# dc-dc_24V_5A_0_2.net
KiCad netlist of a schematic drawn in EAGLE
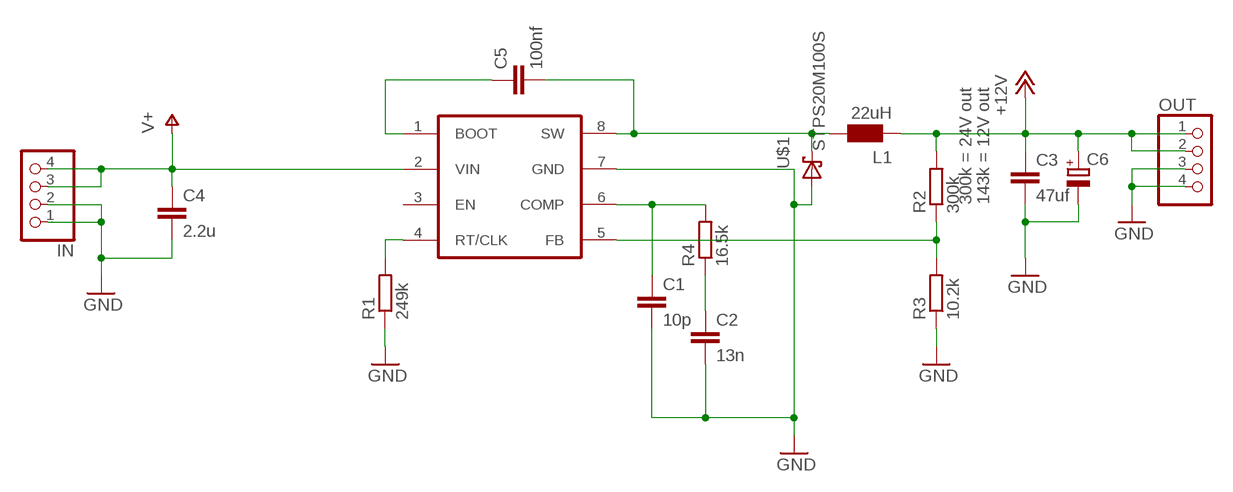
[diagram p0: schematic, sheet 1]

(export (version "E")
  (design (tool "Eeschema 10.0.6"))
  (components
    (comp (ref "C1")
      (value "10p")
      (footprint "eagle-import:C0805")
      (libsource (lib "eagle-import") (part "C-EUC0805"))
    )
    (comp (ref "C2")
      (value "13n")
      (footprint "eagle-import:C1206")
      (libsource (lib "eagle-import") (part "C-EUC1206"))
    )
    (comp (ref "C3")
      (value "47uf")
      (footprint "eagle-import:C1210")
      (libsource (lib "eagle-import") (part "C-EUC1210"))
    )
    (comp (ref "C4")
      (value "2.2u")
      (footprint "eagle-import:C1210")
      (libsource (lib "eagle-import") (part "C-EUC1210"))
    )
    (comp (ref "C5")
      (value "100nf")
      (footprint "eagle-import:C0805")
      (libsource (lib "eagle-import") (part "C-EUC0805"))
    )
    (comp (ref "C6")
      (value "CPOL-EUE2.5-5")
      (footprint "eagle-import:E2,5-5")
      (libsource (lib "eagle-import") (part "CPOL-EUE2.5-5"))
    )
    (comp (ref "IN")
      (value "PINHD-1X4")
      (footprint "eagle-import:1X04")
      (libsource (lib "eagle-import") (part "PINHD-1X4"))
    )
    (comp (ref "L1")
      (value "22uH")
      (footprint "eagle-import:WE-PD_L_XL_XXL")
      (libsource (lib "eagle-import") (part "WE-PD_L/XL/XXL"))
    )
    (comp (ref "OUT")
      (value "PINHD-1X4")
      (footprint "eagle-import:1X04")
      (libsource (lib "eagle-import") (part "PINHD-1X4"))
    )
    (comp (ref "R1")
      (value "249k")
      (footprint "eagle-import:R0805")
      (libsource (lib "eagle-import") (part "R-EU_R0805"))
    )
    (comp (ref "R2")
      (value "300k")
      (footprint "eagle-import:R0805")
      (libsource (lib "eagle-import") (part "R-EU_R0805"))
    )
    (comp (ref "R3")
      (value "10.2k")
      (footprint "eagle-import:R0805")
      (libsource (lib "eagle-import") (part "R-EU_R0805"))
    )
    (comp (ref "R4")
      (value "16.5k")
      (footprint "eagle-import:R0805")
      (libsource (lib "eagle-import") (part "R-EU_R0805"))
    )
    (comp (ref "U$1")
      (value "STPS20M100S")
      (footprint "eagle-import:D2PACK")
      (libsource (lib "eagle-import") (part "STPS20M100S"))
    )
    (comp (ref "U1")
      (value "TPS54560")
      (footprint "eagle-import:SO08-POWERPAD")
      (libsource (lib "eagle-import") (part "TPS54560"))
    )
  )
  (nets
    (net (code "1") (name "+12V") (class "Default")
      (node (ref "C3") (pin "1") (pinfunction "1_1") (pintype "passive"))
      (node (ref "C6") (pin "+") (pinfunction "+_+") (pintype "passive"))
      (node (ref "L1") (pin "2") (pinfunction "1_2") (pintype "passive"))
      (node (ref "OUT") (pin "1") (pinfunction "1_1") (pintype "passive"))
      (node (ref "OUT") (pin "2") (pinfunction "2_2") (pintype "passive"))
      (node (ref "R2") (pin "2") (pinfunction "2_2") (pintype "passive"))
    )
    (net (code "2") (name "GND") (class "Default")
      (node (ref "C1") (pin "2") (pinfunction "2_2") (pintype "passive"))
      (node (ref "C2") (pin "2") (pinfunction "2_2") (pintype "passive"))
      (node (ref "C3") (pin "2") (pinfunction "2_2") (pintype "passive"))
      (node (ref "C4") (pin "2") (pinfunction "2_2") (pintype "passive"))
      (node (ref "C6") (pin "-") (pinfunction "-_-") (pintype "passive"))
      (node (ref "IN") (pin "1") (pinfunction "1_1") (pintype "passive"))
      (node (ref "IN") (pin "2") (pinfunction "2_2") (pintype "passive"))
      (node (ref "OUT") (pin "3") (pinfunction "3_3") (pintype "passive"))
      (node (ref "OUT") (pin "4") (pinfunction "4_4") (pintype "passive"))
      (node (ref "R1") (pin "1") (pinfunction "1_1") (pintype "passive"))
      (node (ref "R3") (pin "1") (pinfunction "1_1") (pintype "passive"))
      (node (ref "U$1") (pin "1") (pinfunction "A_1") (pintype "passive"))
      (node (ref "U$1") (pin "3") (pinfunction "A_3") (pintype "passive"))
      (node (ref "U1") (pin "7") (pinfunction "GND_7") (pintype "input"))
    )
    (net (code "3") (name "Net-(C2-Pad1)") (class "Default")
      (node (ref "C2") (pin "1") (pinfunction "1_1") (pintype "passive"))
      (node (ref "R4") (pin "1") (pinfunction "1_1") (pintype "passive"))
    )
    (net (code "4") (name "Net-(L1-2)") (class "Default")
      (node (ref "C5") (pin "2") (pinfunction "2_2") (pintype "passive"))
      (node (ref "L1") (pin "1") (pinfunction "2_1") (pintype "passive"))
      (node (ref "U$1") (pin "2") (pinfunction "K_2") (pintype "passive"))
      (node (ref "U1") (pin "8") (pinfunction "SW_8") (pintype "output"))
    )
    (net (code "5") (name "Net-(U1-BOOT)") (class "Default")
      (node (ref "C5") (pin "1") (pinfunction "1_1") (pintype "passive"))
      (node (ref "U1") (pin "1") (pinfunction "BOOT_1") (pintype "input"))
    )
    (net (code "6") (name "Net-(U1-COMP)") (class "Default")
      (node (ref "C1") (pin "1") (pinfunction "1_1") (pintype "passive"))
      (node (ref "R4") (pin "2") (pinfunction "2_2") (pintype "passive"))
      (node (ref "U1") (pin "6") (pinfunction "COMP_6") (pintype "output"))
    )
    (net (code "7") (name "Net-(U1-FB)") (class "Default")
      (node (ref "R2") (pin "1") (pinfunction "1_1") (pintype "passive"))
      (node (ref "R3") (pin "2") (pinfunction "2_2") (pintype "passive"))
      (node (ref "U1") (pin "5") (pinfunction "FB_5") (pintype "passive"))
    )
    (net (code "8") (name "Net-(U1-RT{slash}CLK)") (class "Default")
      (node (ref "R1") (pin "2") (pinfunction "2_2") (pintype "passive"))
      (node (ref "U1") (pin "4") (pinfunction "RT/CLK_4") (pintype "input"))
    )
    (net (code "9") (name "V+") (class "Default")
      (node (ref "C4") (pin "1") (pinfunction "1_1") (pintype "passive"))
      (node (ref "IN") (pin "3") (pinfunction "3_3") (pintype "passive"))
      (node (ref "IN") (pin "4") (pinfunction "4_4") (pintype "passive"))
      (node (ref "U1") (pin "2") (pinfunction "VIN_2") (pintype "input"))
    )
    (net (code "10") (name "unconnected-(U1-EN-Pad3)") (class "Default")
      (node (ref "U1") (pin "3") (pinfunction "EN_3") (pintype "input"))
    )
  )
)
